# vfd_driver.net
KiCad netlist of a schematic drawn in EAGLE
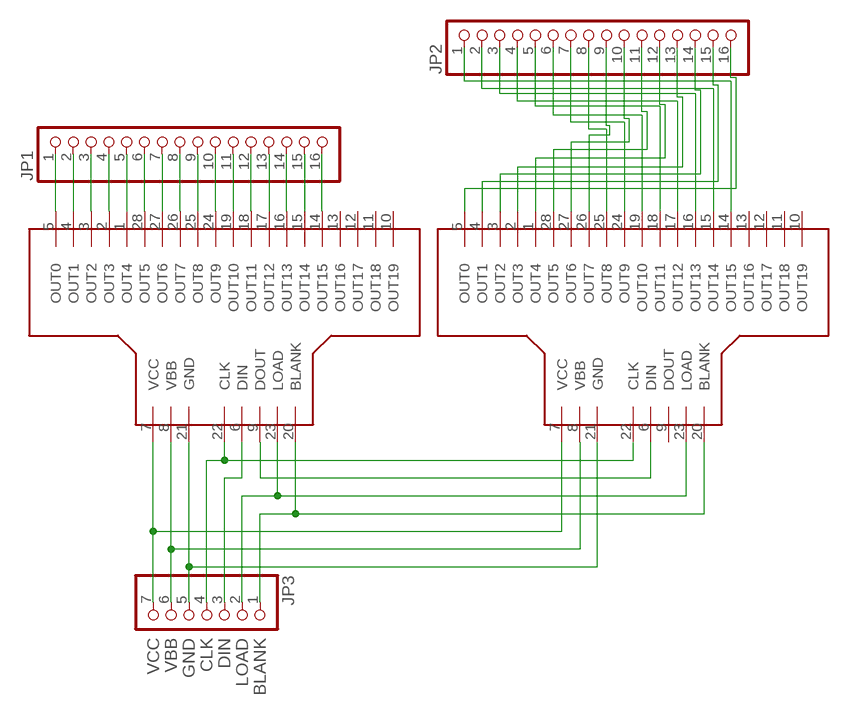
[diagram p0: schematic, sheet 1]

(export (version "E")
  (design (tool "Eeschema 10.0.6"))
  (components
    (comp (ref "JP1")
      (value "PINHD-1X16")
      (footprint "eagle-import:1X16")
      (libsource (lib "eagle-import") (part "PINHD-1X16"))
    )
    (comp (ref "JP2")
      (value "PINHD-1X16")
      (footprint "eagle-import:1X16")
      (libsource (lib "eagle-import") (part "PINHD-1X16"))
    )
    (comp (ref "JP3")
      (value "PINHD-1X7")
      (footprint "eagle-import:1X07")
      (libsource (lib "eagle-import") (part "PINHD-1X7"))
    )
    (comp (ref "U$1")
      (value "MAX6921/31")
      (footprint "eagle-import:TSSOP-28")
      (libsource (lib "eagle-import") (part "MAX6921/31"))
    )
    (comp (ref "U$2")
      (value "MAX6921/31")
      (footprint "eagle-import:TSSOP-28")
      (libsource (lib "eagle-import") (part "MAX6921/31"))
    )
  )
  (nets
    (net (code "1") (name "Net-(U$1-BLANK)") (class "Default")
      (node (ref "JP3") (pin "1") (pinfunction "1_1") (pintype "passive"))
      (node (ref "U$1") (pin "20") (pinfunction "BLANK_20") (pintype "bidirectional"))
      (node (ref "U$2") (pin "20") (pinfunction "BLANK_20") (pintype "bidirectional"))
    )
    (net (code "2") (name "Net-(U$1-CLK)") (class "Default")
      (node (ref "JP3") (pin "4") (pinfunction "4_4") (pintype "passive"))
      (node (ref "U$1") (pin "22") (pinfunction "CLK_22") (pintype "bidirectional"))
      (node (ref "U$2") (pin "22") (pinfunction "CLK_22") (pintype "bidirectional"))
    )
    (net (code "3") (name "Net-(U$1-DIN)") (class "Default")
      (node (ref "JP3") (pin "3") (pinfunction "3_3") (pintype "passive"))
      (node (ref "U$1") (pin "6") (pinfunction "DIN_6") (pintype "bidirectional"))
    )
    (net (code "4") (name "Net-(U$1-DOUT)") (class "Default")
      (node (ref "U$1") (pin "9") (pinfunction "DOUT_9") (pintype "bidirectional"))
      (node (ref "U$2") (pin "6") (pinfunction "DIN_6") (pintype "bidirectional"))
    )
    (net (code "5") (name "Net-(U$1-GND)") (class "Default")
      (node (ref "JP3") (pin "5") (pinfunction "5_5") (pintype "passive"))
      (node (ref "U$1") (pin "21") (pinfunction "GND_21") (pintype "bidirectional"))
      (node (ref "U$2") (pin "21") (pinfunction "GND_21") (pintype "bidirectional"))
    )
    (net (code "6") (name "Net-(U$1-LOAD)") (class "Default")
      (node (ref "JP3") (pin "2") (pinfunction "2_2") (pintype "passive"))
      (node (ref "U$1") (pin "23") (pinfunction "LOAD_23") (pintype "bidirectional"))
      (node (ref "U$2") (pin "23") (pinfunction "LOAD_23") (pintype "bidirectional"))
    )
    (net (code "7") (name "Net-(U$1-OUT0)") (class "Default")
      (node (ref "JP1") (pin "1") (pinfunction "1_1") (pintype "passive"))
      (node (ref "U$1") (pin "5") (pinfunction "OUT0_5") (pintype "bidirectional"))
    )
    (net (code "8") (name "Net-(U$1-OUT1)") (class "Default")
      (node (ref "JP1") (pin "2") (pinfunction "2_2") (pintype "passive"))
      (node (ref "U$1") (pin "4") (pinfunction "OUT1_4") (pintype "bidirectional"))
    )
    (net (code "9") (name "Net-(U$1-OUT2)") (class "Default")
      (node (ref "JP1") (pin "3") (pinfunction "3_3") (pintype "passive"))
      (node (ref "U$1") (pin "3") (pinfunction "OUT2_3") (pintype "bidirectional"))
    )
    (net (code "10") (name "Net-(U$1-OUT3)") (class "Default")
      (node (ref "JP1") (pin "4") (pinfunction "4_4") (pintype "passive"))
      (node (ref "U$1") (pin "2") (pinfunction "OUT3_2") (pintype "bidirectional"))
    )
    (net (code "11") (name "Net-(U$1-OUT4)") (class "Default")
      (node (ref "JP1") (pin "5") (pinfunction "5_5") (pintype "passive"))
      (node (ref "U$1") (pin "1") (pinfunction "OUT4_1") (pintype "bidirectional"))
    )
    (net (code "12") (name "Net-(U$1-OUT5)") (class "Default")
      (node (ref "JP1") (pin "6") (pinfunction "6_6") (pintype "passive"))
      (node (ref "U$1") (pin "28") (pinfunction "OUT5_28") (pintype "bidirectional"))
    )
    (net (code "13") (name "Net-(U$1-OUT6)") (class "Default")
      (node (ref "JP1") (pin "7") (pinfunction "7_7") (pintype "passive"))
      (node (ref "U$1") (pin "27") (pinfunction "OUT6_27") (pintype "bidirectional"))
    )
    (net (code "14") (name "Net-(U$1-OUT7)") (class "Default")
      (node (ref "JP1") (pin "8") (pinfunction "8_8") (pintype "passive"))
      (node (ref "U$1") (pin "26") (pinfunction "OUT7_26") (pintype "bidirectional"))
    )
    (net (code "15") (name "Net-(U$1-OUT8)") (class "Default")
      (node (ref "JP1") (pin "9") (pinfunction "9_9") (pintype "passive"))
      (node (ref "U$1") (pin "25") (pinfunction "OUT8_25") (pintype "bidirectional"))
    )
    (net (code "16") (name "Net-(U$1-OUT9)") (class "Default")
      (node (ref "JP1") (pin "10") (pinfunction "10_10") (pintype "passive"))
      (node (ref "U$1") (pin "24") (pinfunction "OUT9_24") (pintype "bidirectional"))
    )
    (net (code "17") (name "Net-(U$1-OUT10)") (class "Default")
      (node (ref "JP1") (pin "11") (pinfunction "11_11") (pintype "passive"))
      (node (ref "U$1") (pin "19") (pinfunction "OUT10_19") (pintype "bidirectional"))
    )
    (net (code "18") (name "Net-(U$1-OUT11)") (class "Default")
      (node (ref "JP1") (pin "12") (pinfunction "12_12") (pintype "passive"))
      (node (ref "U$1") (pin "18") (pinfunction "OUT11_18") (pintype "bidirectional"))
    )
    (net (code "19") (name "Net-(U$1-OUT12)") (class "Default")
      (node (ref "JP1") (pin "13") (pinfunction "13_13") (pintype "passive"))
      (node (ref "U$1") (pin "17") (pinfunction "OUT12_17") (pintype "bidirectional"))
    )
    (net (code "20") (name "Net-(U$1-OUT13)") (class "Default")
      (node (ref "JP1") (pin "14") (pinfunction "14_14") (pintype "passive"))
      (node (ref "U$1") (pin "16") (pinfunction "OUT13_16") (pintype "bidirectional"))
    )
    (net (code "21") (name "Net-(U$1-OUT14)") (class "Default")
      (node (ref "JP1") (pin "15") (pinfunction "15_15") (pintype "passive"))
      (node (ref "U$1") (pin "15") (pinfunction "OUT14_15") (pintype "bidirectional"))
    )
    (net (code "22") (name "Net-(U$1-OUT15)") (class "Default")
      (node (ref "JP1") (pin "16") (pinfunction "16_16") (pintype "passive"))
      (node (ref "U$1") (pin "14") (pinfunction "OUT15_14") (pintype "bidirectional"))
    )
    (net (code "23") (name "Net-(U$1-VBB)") (class "Default")
      (node (ref "JP3") (pin "6") (pinfunction "6_6") (pintype "passive"))
      (node (ref "U$1") (pin "8") (pinfunction "VBB_8") (pintype "bidirectional"))
      (node (ref "U$2") (pin "8") (pinfunction "VBB_8") (pintype "bidirectional"))
    )
    (net (code "24") (name "Net-(U$1-VCC)") (class "Default")
      (node (ref "JP3") (pin "7") (pinfunction "7_7") (pintype "passive"))
      (node (ref "U$1") (pin "7") (pinfunction "VCC_7") (pintype "bidirectional"))
      (node (ref "U$2") (pin "7") (pinfunction "VCC_7") (pintype "bidirectional"))
    )
    (net (code "25") (name "Net-(U$2-OUT0)") (class "Default")
      (node (ref "JP2") (pin "16") (pinfunction "16_16") (pintype "passive"))
      (node (ref "U$2") (pin "5") (pinfunction "OUT0_5") (pintype "bidirectional"))
    )
    (net (code "26") (name "Net-(U$2-OUT1)") (class "Default")
      (node (ref "JP2") (pin "15") (pinfunction "15_15") (pintype "passive"))
      (node (ref "U$2") (pin "4") (pinfunction "OUT1_4") (pintype "bidirectional"))
    )
    (net (code "27") (name "Net-(U$2-OUT2)") (class "Default")
      (node (ref "JP2") (pin "14") (pinfunction "14_14") (pintype "passive"))
      (node (ref "U$2") (pin "3") (pinfunction "OUT2_3") (pintype "bidirectional"))
    )
    (net (code "28") (name "Net-(U$2-OUT3)") (class "Default")
      (node (ref "JP2") (pin "13") (pinfunction "13_13") (pintype "passive"))
      (node (ref "U$2") (pin "2") (pinfunction "OUT3_2") (pintype "bidirectional"))
    )
    (net (code "29") (name "Net-(U$2-OUT4)") (class "Default")
      (node (ref "JP2") (pin "12") (pinfunction "12_12") (pintype "passive"))
      (node (ref "U$2") (pin "1") (pinfunction "OUT4_1") (pintype "bidirectional"))
    )
    (net (code "30") (name "Net-(U$2-OUT5)") (class "Default")
      (node (ref "JP2") (pin "11") (pinfunction "11_11") (pintype "passive"))
      (node (ref "U$2") (pin "28") (pinfunction "OUT5_28") (pintype "bidirectional"))
    )
    (net (code "31") (name "Net-(U$2-OUT6)") (class "Default")
      (node (ref "JP2") (pin "10") (pinfunction "10_10") (pintype "passive"))
      (node (ref "U$2") (pin "27") (pinfunction "OUT6_27") (pintype "bidirectional"))
    )
    (net (code "32") (name "Net-(U$2-OUT7)") (class "Default")
      (node (ref "JP2") (pin "9") (pinfunction "9_9") (pintype "passive"))
      (node (ref "U$2") (pin "26") (pinfunction "OUT7_26") (pintype "bidirectional"))
    )
    (net (code "33") (name "Net-(U$2-OUT8)") (class "Default")
      (node (ref "JP2") (pin "8") (pinfunction "8_8") (pintype "passive"))
      (node (ref "U$2") (pin "25") (pinfunction "OUT8_25") (pintype "bidirectional"))
    )
    (net (code "34") (name "Net-(U$2-OUT9)") (class "Default")
      (node (ref "JP2") (pin "7") (pinfunction "7_7") (pintype "passive"))
      (node (ref "U$2") (pin "24") (pinfunction "OUT9_24") (pintype "bidirectional"))
    )
    (net (code "35") (name "Net-(U$2-OUT10)") (class "Default")
      (node (ref "JP2") (pin "6") (pinfunction "6_6") (pintype "passive"))
      (node (ref "U$2") (pin "19") (pinfunction "OUT10_19") (pintype "bidirectional"))
    )
    (net (code "36") (name "Net-(U$2-OUT11)") (class "Default")
      (node (ref "JP2") (pin "5") (pinfunction "5_5") (pintype "passive"))
      (node (ref "U$2") (pin "18") (pinfunction "OUT11_18") (pintype "bidirectional"))
    )
    (net (code "37") (name "Net-(U$2-OUT12)") (class "Default")
      (node (ref "JP2") (pin "4") (pinfunction "4_4") (pintype "passive"))
      (node (ref "U$2") (pin "17") (pinfunction "OUT12_17") (pintype "bidirectional"))
    )
    (net (code "38") (name "Net-(U$2-OUT13)") (class "Default")
      (node (ref "JP2") (pin "3") (pinfunction "3_3") (pintype "passive"))
      (node (ref "U$2") (pin "16") (pinfunction "OUT13_16") (pintype "bidirectional"))
    )
    (net (code "39") (name "Net-(U$2-OUT14)") (class "Default")
      (node (ref "JP2") (pin "2") (pinfunction "2_2") (pintype "passive"))
      (node (ref "U$2") (pin "15") (pinfunction "OUT14_15") (pintype "bidirectional"))
    )
    (net (code "40") (name "Net-(U$2-OUT15)") (class "Default")
      (node (ref "JP2") (pin "1") (pinfunction "1_1") (pintype "passive"))
      (node (ref "U$2") (pin "14") (pinfunction "OUT15_14") (pintype "bidirectional"))
    )
    (net (code "41") (name "unconnected-(U$1-OUT16-Pad13)") (class "Default")
      (node (ref "U$1") (pin "13") (pinfunction "OUT16_13") (pintype "bidirectional"))
    )
    (net (code "42") (name "unconnected-(U$1-OUT17-Pad12)") (class "Default")
      (node (ref "U$1") (pin "12") (pinfunction "OUT17_12") (pintype "bidirectional"))
    )
    (net (code "43") (name "unconnected-(U$1-OUT18-Pad11)") (class "Default")
      (node (ref "U$1") (pin "11") (pinfunction "OUT18_11") (pintype "bidirectional"))
    )
    (net (code "44") (name "unconnected-(U$1-OUT19-Pad10)") (class "Default")
      (node (ref "U$1") (pin "10") (pinfunction "OUT19_10") (pintype "bidirectional"))
    )
    (net (code "45") (name "unconnected-(U$2-DOUT-Pad9)") (class "Default")
      (node (ref "U$2") (pin "9") (pinfunction "DOUT_9") (pintype "bidirectional"))
    )
    (net (code "46") (name "unconnected-(U$2-OUT16-Pad13)") (class "Default")
      (node (ref "U$2") (pin "13") (pinfunction "OUT16_13") (pintype "bidirectional"))
    )
    (net (code "47") (name "unconnected-(U$2-OUT17-Pad12)") (class "Default")
      (node (ref "U$2") (pin "12") (pinfunction "OUT17_12") (pintype "bidirectional"))
    )
    (net (code "48") (name "unconnected-(U$2-OUT18-Pad11)") (class "Default")
      (node (ref "U$2") (pin "11") (pinfunction "OUT18_11") (pintype "bidirectional"))
    )
    (net (code "49") (name "unconnected-(U$2-OUT19-Pad10)") (class "Default")
      (node (ref "U$2") (pin "10") (pinfunction "OUT19_10") (pintype "bidirectional"))
    )
  )
)
